# 5-SD-Card.net
KiCad netlist of a schematic drawn in Altium Designer
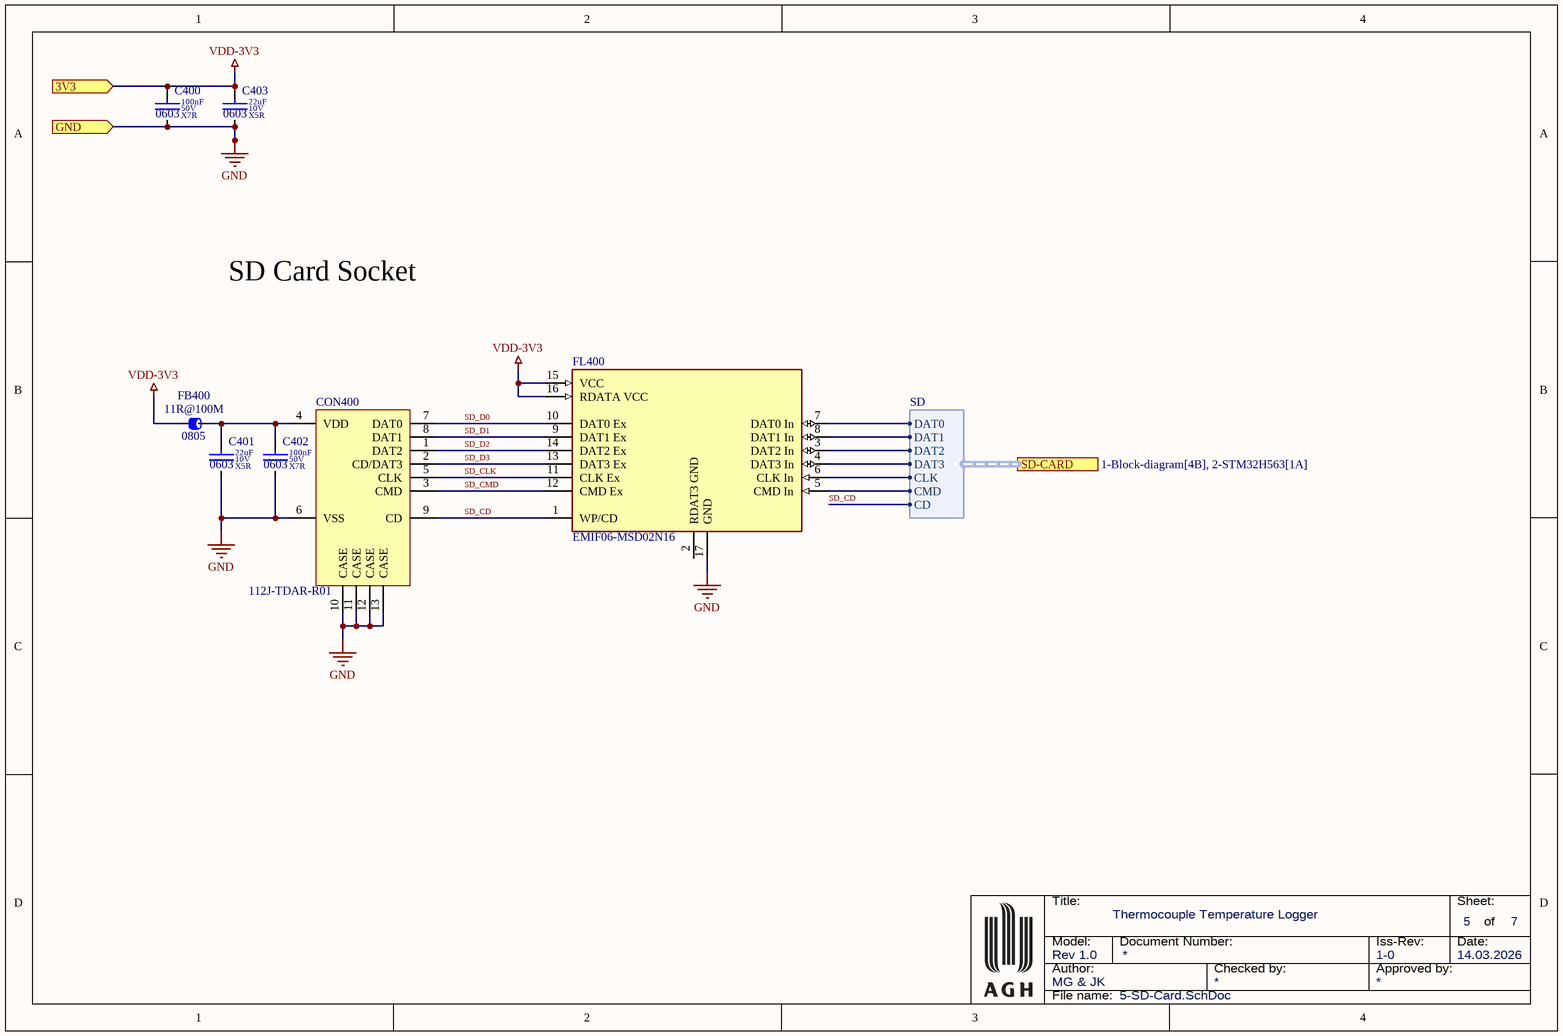
[diagram p0: 5-SD-Card.SchDoc]

(export (version "E")
  (design (tool "Eeschema 10.0.6"))
  (components
    (comp (ref "C400")
      (value "100nF")
      (footprint "C_0603_1608")
      (description "Capacitor")
      (fields
        (field (name "DIELECTRIC") "X7R")
        (field (name "VOLTAGE") "50V")
        (field (name "SCH_FOOTPRINT") "0603")
        (field (name "PART NUMBER") "C_100nF_50V_X7R_0603_10_AECQ1")
        (field (name "MANUFACTURER") "Murata")
      )
      (libsource (lib "Library") (part "C"))
    )
    (comp (ref "C401")
      (value "22uF")
      (footprint "C_0603_1608")
      (description "Capacitor")
      (fields
        (field (name "DIELECTRIC") "X5R")
        (field (name "VOLTAGE") "10V")
        (field (name "SCH_FOOTPRINT") "0603")
        (field (name "PART NUMBER") "C_22uF_10V_X5R_0603_20")
        (field (name "MANUFACTURER") "Murata")
      )
      (libsource (lib "Library") (part "C"))
    )
    (comp (ref "C402")
      (value "100nF")
      (footprint "C_0603_1608")
      (description "Capacitor")
      (fields
        (field (name "DIELECTRIC") "X7R")
        (field (name "VOLTAGE") "50V")
        (field (name "SCH_FOOTPRINT") "0603")
        (field (name "PART NUMBER") "C_100nF_50V_X7R_0603_10_AECQ1")
        (field (name "MANUFACTURER") "Murata")
      )
      (libsource (lib "Library") (part "C"))
    )
    (comp (ref "C403")
      (value "22uF")
      (footprint "C_0603_1608")
      (description "Capacitor")
      (fields
        (field (name "DIELECTRIC") "X5R")
        (field (name "VOLTAGE") "10V")
        (field (name "SCH_FOOTPRINT") "0603")
        (field (name "PART NUMBER") "C_22uF_10V_X5R_0603_20")
        (field (name "MANUFACTURER") "Murata")
      )
      (libsource (lib "Library") (part "C"))
    )
    (comp (ref "CON400")
      (value "112J-TDAR-R01")
      (footprint "112J-TDAR-R01")
      (libsource (lib "GG_LIB") (part "112J-TDAR-R01"))
    )
    (comp (ref "FB400")
      (value "11R@100M")
      (footprint "FB_0805_2012")
      (description "Ferrite Bead")
      (fields
        (field (name "SCH_FOOTPRINT") "0805")
        (field (name "PART NUMBER") "FB_2508051107Y0")
        (field (name "MANUFACTURER") "Fair-Rite")
      )
      (libsource (lib "Library") (part "FB"))
    )
    (comp (ref "FL400")
      (value "EMIF06-MSD02N16")
      (footprint "FP-EMIF06-MSD02N16-MFG")
      (description "FILTER RC(PI) 45 OHM/20PF SMD")
      (libsource (lib "Altium Content Vault") (part "46d5cc2144889aedbacbd23965f839f"))
    )
  )
  (nets
    (net (code "2") (name "/CLK") (class "Default")
      (node (ref "FL400") (pin "6") (pinfunction "CLK_In_6") (pintype "input"))
    )
    (net (code "3") (name "/CMD") (class "Default")
      (node (ref "FL400") (pin "5") (pinfunction "CMD_In_5") (pintype "input"))
    )
    (net (code "4") (name "/DAT0") (class "Default")
      (node (ref "FL400") (pin "7") (pinfunction "DAT0_In_7") (pintype "bidirectional"))
    )
    (net (code "5") (name "/DAT1") (class "Default")
      (node (ref "FL400") (pin "8") (pinfunction "DAT1_In_8") (pintype "bidirectional"))
    )
    (net (code "6") (name "/DAT2") (class "Default")
      (node (ref "FL400") (pin "3") (pinfunction "DAT2_In_3") (pintype "bidirectional"))
    )
    (net (code "7") (name "/DAT3") (class "Default")
      (node (ref "FL400") (pin "4") (pinfunction "DAT3_In_4") (pintype "bidirectional"))
    )
    (net (code "8") (name "/SD_CD") (class "Default")
      (node (ref "CON400") (pin "9") (pinfunction "CD_9") (pintype "passive"))
      (node (ref "FL400") (pin "1") (pinfunction "WP/CD_1") (pintype "passive"))
    )
    (net (code "9") (name "/SD_CLK") (class "Default")
      (node (ref "CON400") (pin "5") (pinfunction "CLK_5") (pintype "passive"))
      (node (ref "FL400") (pin "11") (pinfunction "CLK_Ex_11") (pintype "passive"))
    )
    (net (code "10") (name "/SD_CMD") (class "Default")
      (node (ref "CON400") (pin "3") (pinfunction "CMD_3") (pintype "passive"))
      (node (ref "FL400") (pin "12") (pinfunction "CMD_Ex_12") (pintype "passive"))
    )
    (net (code "11") (name "/SD_D0") (class "Default")
      (node (ref "CON400") (pin "7") (pinfunction "DAT0_7") (pintype "passive"))
      (node (ref "FL400") (pin "10") (pinfunction "DAT0_Ex_10") (pintype "passive"))
    )
    (net (code "12") (name "/SD_D1") (class "Default")
      (node (ref "CON400") (pin "8") (pinfunction "DAT1_8") (pintype "passive"))
      (node (ref "FL400") (pin "9") (pinfunction "DAT1_Ex_9") (pintype "passive"))
    )
    (net (code "13") (name "/SD_D2") (class "Default")
      (node (ref "CON400") (pin "1") (pinfunction "DAT2_1") (pintype "passive"))
      (node (ref "FL400") (pin "14") (pinfunction "DAT2_Ex_14") (pintype "passive"))
    )
    (net (code "14") (name "/SD_D3") (class "Default")
      (node (ref "CON400") (pin "2") (pinfunction "CD/DAT3_2") (pintype "passive"))
      (node (ref "FL400") (pin "13") (pinfunction "DAT3_Ex_13") (pintype "passive"))
    )
    (net (code "16") (name "GND") (class "Default")
      (node (ref "C400") (pin "2") (pinfunction "2_2") (pintype "passive"))
      (node (ref "C401") (pin "2") (pinfunction "2_2") (pintype "passive"))
      (node (ref "C402") (pin "2") (pinfunction "2_2") (pintype "passive"))
      (node (ref "C403") (pin "2") (pinfunction "2_2") (pintype "passive"))
      (node (ref "CON400") (pin "10") (pinfunction "CASE_10") (pintype "passive"))
      (node (ref "CON400") (pin "11") (pinfunction "CASE_11") (pintype "passive"))
      (node (ref "CON400") (pin "12") (pinfunction "CASE_12") (pintype "passive"))
      (node (ref "CON400") (pin "13") (pinfunction "CASE_13") (pintype "passive"))
      (node (ref "CON400") (pin "6") (pinfunction "VSS_6") (pintype "passive"))
      (node (ref "FL400") (pin "17") (pinfunction "GND_17") (pintype "passive"))
    )
    (net (code "17") (name "Net-(CON400-VDD)") (class "Default")
      (node (ref "C401") (pin "1") (pinfunction "1_1") (pintype "passive"))
      (node (ref "C402") (pin "1") (pinfunction "1_1") (pintype "passive"))
      (node (ref "CON400") (pin "4") (pinfunction "VDD_4") (pintype "passive"))
      (node (ref "FB400") (pin "2") (pintype "passive"))
    )
    (net (code "18") (name "VDD-3V3") (class "Default")
      (node (ref "C400") (pin "1") (pinfunction "1_1") (pintype "passive"))
      (node (ref "C403") (pin "1") (pinfunction "1_1") (pintype "passive"))
      (node (ref "FB400") (pin "1") (pintype "passive"))
      (node (ref "FL400") (pin "15") (pinfunction "VCC_15") (pintype "input"))
      (node (ref "FL400") (pin "16") (pinfunction "RDATA_VCC_16") (pintype "input"))
    )
    (net (code "19") (name "unconnected-(FL400-RDAT3_GND-Pad2)") (class "Default")
      (node (ref "FL400") (pin "2") (pinfunction "RDAT3_GND_2") (pintype "power_in"))
    )
  )
)
